# Fri3D_2020_Sweet4x4_01.net
KiCad netlist of a schematic drawn in Altium Designer
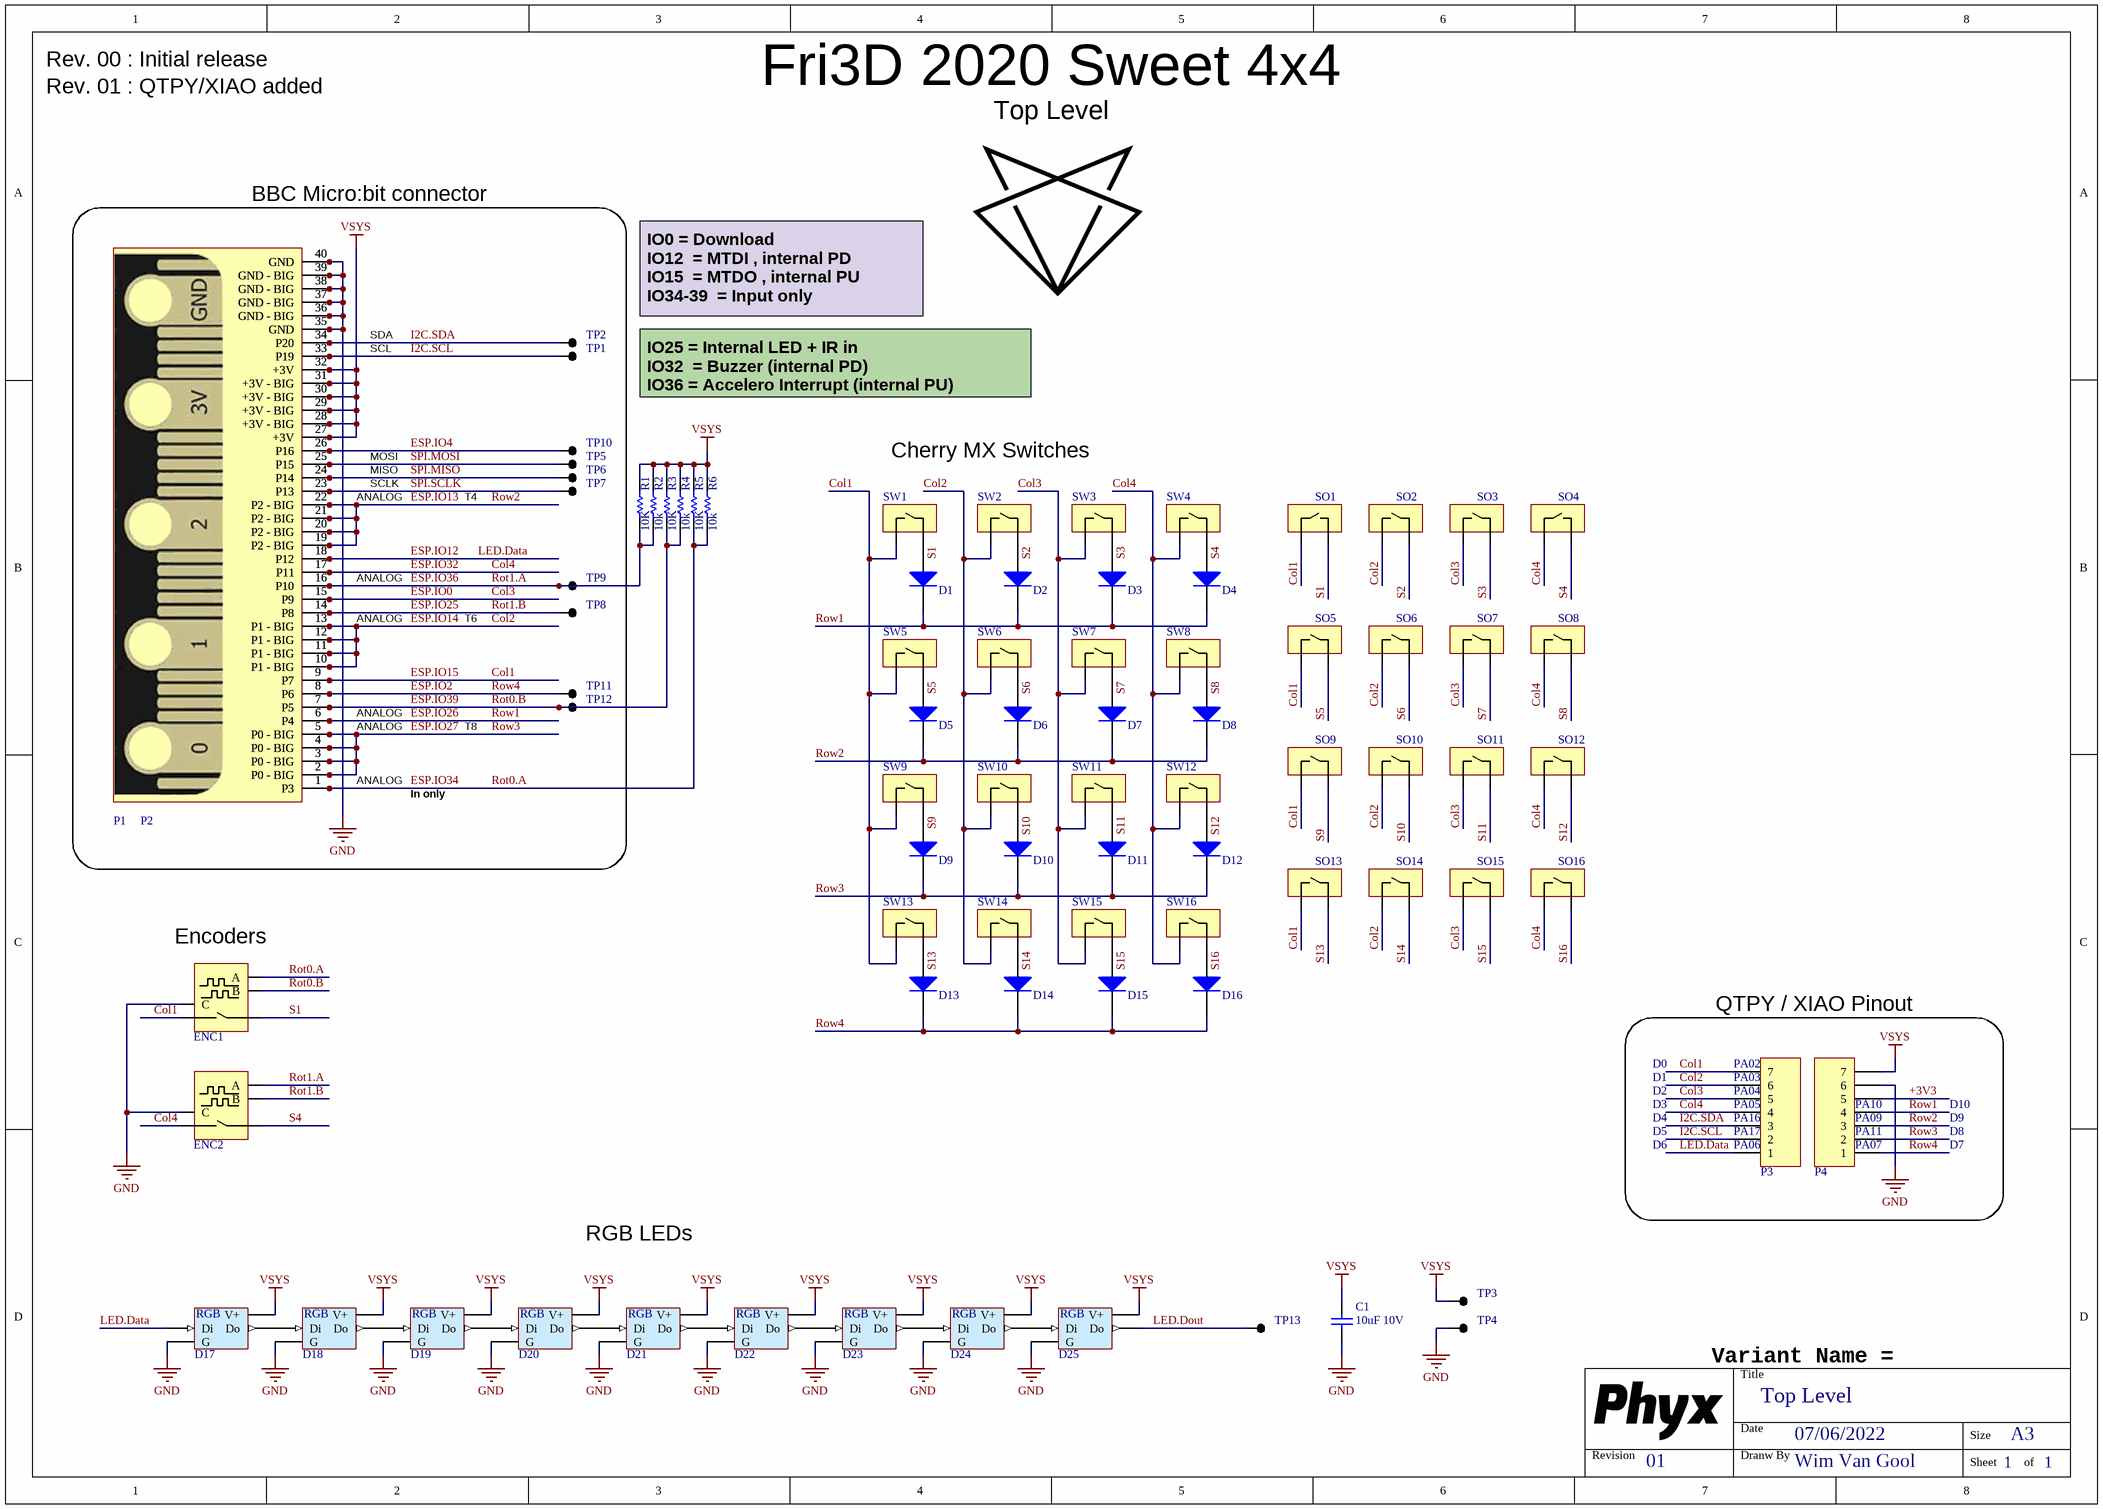
[diagram p0: Fri3D_2020_Sweet4x4_01.SchDoc]

(export (version "E")
  (design (tool "Eeschema 10.0.6"))
  (components
    (comp (ref "C1")
      (value "10uF 10V")
      (footprint "C0805_N")
      (description "Capacitor Ceramic")
      (fields (field (name "Comment") "CAP_CERAMIC"))
      (libsource (lib "Phyx_Components") (part "CAP_CERAMIC"))
    )
    (comp (ref "D1")
      (value "1N4148 100V 200mA 1Vf@10mA")
      (footprint "DO-35")
      (description "Default Diode")
      (libsource (lib "Phyx_Components") (part "DIODE_AC"))
    )
    (comp (ref "D2")
      (value "1N4148 100V 200mA 1Vf@10mA")
      (footprint "DO-35")
      (description "Default Diode")
      (libsource (lib "Phyx_Components") (part "DIODE_AC"))
    )
    (comp (ref "D3")
      (value "1N4148 100V 200mA 1Vf@10mA")
      (footprint "DO-35")
      (description "Default Diode")
      (libsource (lib "Phyx_Components") (part "DIODE_AC"))
    )
    (comp (ref "D4")
      (value "1N4148 100V 200mA 1Vf@10mA")
      (footprint "DO-35")
      (description "Default Diode")
      (libsource (lib "Phyx_Components") (part "DIODE_AC"))
    )
    (comp (ref "D5")
      (value "1N4148 100V 200mA 1Vf@10mA")
      (footprint "DO-35")
      (description "Default Diode")
      (libsource (lib "Phyx_Components") (part "DIODE_AC"))
    )
    (comp (ref "D6")
      (value "1N4148 100V 200mA 1Vf@10mA")
      (footprint "DO-35")
      (description "Default Diode")
      (libsource (lib "Phyx_Components") (part "DIODE_AC"))
    )
    (comp (ref "D7")
      (value "1N4148 100V 200mA 1Vf@10mA")
      (footprint "DO-35")
      (description "Default Diode")
      (libsource (lib "Phyx_Components") (part "DIODE_AC"))
    )
    (comp (ref "D8")
      (value "1N4148 100V 200mA 1Vf@10mA")
      (footprint "DO-35")
      (description "Default Diode")
      (libsource (lib "Phyx_Components") (part "DIODE_AC"))
    )
    (comp (ref "D9")
      (value "1N4148 100V 200mA 1Vf@10mA")
      (footprint "DO-35")
      (description "Default Diode")
      (libsource (lib "Phyx_Components") (part "DIODE_AC"))
    )
    (comp (ref "D10")
      (value "1N4148 100V 200mA 1Vf@10mA")
      (footprint "DO-35")
      (description "Default Diode")
      (libsource (lib "Phyx_Components") (part "DIODE_AC"))
    )
    (comp (ref "D11")
      (value "1N4148 100V 200mA 1Vf@10mA")
      (footprint "DO-35")
      (description "Default Diode")
      (libsource (lib "Phyx_Components") (part "DIODE_AC"))
    )
    (comp (ref "D12")
      (value "1N4148 100V 200mA 1Vf@10mA")
      (footprint "DO-35")
      (description "Default Diode")
      (libsource (lib "Phyx_Components") (part "DIODE_AC"))
    )
    (comp (ref "D13")
      (value "1N4148 100V 200mA 1Vf@10mA")
      (footprint "DO-35")
      (description "Default Diode")
      (libsource (lib "Phyx_Components") (part "DIODE_AC"))
    )
    (comp (ref "D14")
      (value "1N4148 100V 200mA 1Vf@10mA")
      (footprint "DO-35")
      (description "Default Diode")
      (libsource (lib "Phyx_Components") (part "DIODE_AC"))
    )
    (comp (ref "D15")
      (value "1N4148 100V 200mA 1Vf@10mA")
      (footprint "DO-35")
      (description "Default Diode")
      (libsource (lib "Phyx_Components") (part "DIODE_AC"))
    )
    (comp (ref "D16")
      (value "1N4148 100V 200mA 1Vf@10mA")
      (footprint "DO-35")
      (description "Default Diode")
      (libsource (lib "Phyx_Components") (part "DIODE_AC"))
    )
    (comp (ref "D17")
      (value "WS2812 based digital RGB LED 5050 Black package")
      (footprint "LED_5050_WS2812B_BLACK")
      (description "=Description")
      (libsource (lib "Phyx_Components") (part "LED_RGB_WS2812B_5050"))
    )
    (comp (ref "D18")
      (value "WS2812 based digital RGB LED 5050 Black package")
      (footprint "LED_5050_WS2812B_BLACK")
      (description "=Description")
      (libsource (lib "Phyx_Components") (part "LED_RGB_WS2812B_5050"))
    )
    (comp (ref "D19")
      (value "WS2812 based digital RGB LED 5050 Black package")
      (footprint "LED_5050_WS2812B_BLACK")
      (description "=Description")
      (libsource (lib "Phyx_Components") (part "LED_RGB_WS2812B_5050"))
    )
    (comp (ref "D20")
      (value "WS2812 based digital RGB LED 5050 Black package")
      (footprint "LED_5050_WS2812B_BLACK")
      (description "=Description")
      (libsource (lib "Phyx_Components") (part "LED_RGB_WS2812B_5050"))
    )
    (comp (ref "D21")
      (value "WS2812 based digital RGB LED 5050 Black package")
      (footprint "LED_5050_WS2812B_BLACK")
      (description "=Description")
      (libsource (lib "Phyx_Components") (part "LED_RGB_WS2812B_5050"))
    )
    (comp (ref "D22")
      (value "WS2812 based digital RGB LED 5050 Black package")
      (footprint "LED_5050_WS2812B_BLACK")
      (description "=Description")
      (libsource (lib "Phyx_Components") (part "LED_RGB_WS2812B_5050"))
    )
    (comp (ref "D23")
      (value "WS2812 based digital RGB LED 5050 Black package")
      (footprint "LED_5050_WS2812B_BLACK")
      (description "=Description")
      (libsource (lib "Phyx_Components") (part "LED_RGB_WS2812B_5050"))
    )
    (comp (ref "D24")
      (value "WS2812 based digital RGB LED 5050 Black package")
      (footprint "LED_5050_WS2812B_BLACK")
      (description "=Description")
      (libsource (lib "Phyx_Components") (part "LED_RGB_WS2812B_5050"))
    )
    (comp (ref "D25")
      (value "WS2812 based digital RGB LED 5050 Black package")
      (footprint "LED_5050_WS2812B_BLACK")
      (description "=Description")
      (libsource (lib "Phyx_Components") (part "LED_RGB_WS2812B_5050"))
    )
    (comp (ref "ENC1")
      (value "Rotary Encoder with Switch")
      (footprint "PEC11-4215F-S0024")
      (libsource (lib "Phyx_Components") (part "ROT_ENC_3P_SW"))
    )
    (comp (ref "ENC2")
      (value "Rotary Encoder with Switch")
      (footprint "PEC11-4215F-S0024")
      (libsource (lib "Phyx_Components") (part "ROT_ENC_3P_SW"))
    )
    (comp (ref "P1")
      (value "MicroBit 90deg connector Cylconn")
      (footprint "MicroBIT_CYLCONN_SMD_90")
      (libsource (lib "Phyx_Components") (part "Header 40_MicroBit"))
    )
    (comp (ref "P2")
      (value "MicroBit 180deg connector Cylconn")
      (footprint "MicroBIT_CYLCONN_SMD_180")
      (libsource (lib "Phyx_Components") (part "Header 40_MicroBit"))
    )
    (comp (ref "P3") (value "Header 7") (footprint "HDR1X7") (libsource (lib "") (part "Header 7_1")))
    (comp (ref "P4")
      (value "Header 7")
      (footprint "HDR1X7")
      (libsource (lib "Phyx_Components") (part "Header 7"))
    )
    (comp (ref "R1")
      (value "10K")
      (footprint "R0603_N")
      (fields (field (name "Comment") "RESISTOR"))
      (libsource (lib "Phyx_Components") (part "RESISTOR"))
    )
    (comp (ref "R2")
      (value "10k")
      (footprint "RES_10mm")
      (fields (field (name "Comment") "RESISTOR"))
      (libsource (lib "Phyx_Components") (part "RESISTOR"))
    )
    (comp (ref "R3")
      (value "10K")
      (footprint "R0603_N")
      (fields (field (name "Comment") "RESISTOR"))
      (libsource (lib "Phyx_Components") (part "RESISTOR"))
    )
    (comp (ref "R4")
      (value "10k")
      (footprint "RES_10mm")
      (fields (field (name "Comment") "RESISTOR"))
      (libsource (lib "Phyx_Components") (part "RESISTOR"))
    )
    (comp (ref "R5")
      (value "10K")
      (footprint "R0603_N")
      (fields (field (name "Comment") "RESISTOR"))
      (libsource (lib "Phyx_Components") (part "RESISTOR"))
    )
    (comp (ref "R6")
      (value "10k")
      (footprint "RES_10mm")
      (fields (field (name "Comment") "RESISTOR"))
      (libsource (lib "Phyx_Components") (part "RESISTOR"))
    )
    (comp (ref "SO1")
      (value "Kailh MX Socket")
      (footprint "Kailh_MX_Socket")
      (libsource (lib "") (part "SW_TACT_1"))
    )
    (comp (ref "SO2")
      (value "Kailh MX Socket")
      (footprint "Kailh_MX_Socket")
      (libsource (lib "Phyx_Components") (part "SW_TACT"))
    )
    (comp (ref "SO3")
      (value "Kailh MX Socket")
      (footprint "Kailh_MX_Socket")
      (libsource (lib "Phyx_Components") (part "SW_TACT"))
    )
    (comp (ref "SO4")
      (value "Kailh MX Socket")
      (footprint "Kailh_MX_Socket")
      (libsource (lib "") (part "SW_TACT_1"))
    )
    (comp (ref "SO5")
      (value "Kailh MX Socket")
      (footprint "Kailh_MX_Socket")
      (libsource (lib "Phyx_Components") (part "SW_TACT"))
    )
    (comp (ref "SO6")
      (value "Kailh MX Socket")
      (footprint "Kailh_MX_Socket")
      (libsource (lib "Phyx_Components") (part "SW_TACT"))
    )
    (comp (ref "SO7")
      (value "Kailh MX Socket")
      (footprint "Kailh_MX_Socket")
      (libsource (lib "Phyx_Components") (part "SW_TACT"))
    )
    (comp (ref "SO8")
      (value "Kailh MX Socket")
      (footprint "Kailh_MX_Socket")
      (libsource (lib "Phyx_Components") (part "SW_TACT"))
    )
    (comp (ref "SO9")
      (value "Kailh MX Socket")
      (footprint "Kailh_MX_Socket")
      (libsource (lib "Phyx_Components") (part "SW_TACT"))
    )
    (comp (ref "SO10")
      (value "Kailh MX Socket")
      (footprint "Kailh_MX_Socket")
      (libsource (lib "Phyx_Components") (part "SW_TACT"))
    )
    (comp (ref "SO11")
      (value "Kailh MX Socket")
      (footprint "Kailh_MX_Socket")
      (libsource (lib "Phyx_Components") (part "SW_TACT"))
    )
    (comp (ref "SO12")
      (value "Kailh MX Socket")
      (footprint "Kailh_MX_Socket")
      (libsource (lib "Phyx_Components") (part "SW_TACT"))
    )
    (comp (ref "SO13")
      (value "Kailh MX Socket")
      (footprint "Kailh_MX_Socket")
      (libsource (lib "Phyx_Components") (part "SW_TACT"))
    )
    (comp (ref "SO14")
      (value "Kailh MX Socket")
      (footprint "Kailh_MX_Socket")
      (libsource (lib "Phyx_Components") (part "SW_TACT"))
    )
    (comp (ref "SO15")
      (value "Kailh MX Socket")
      (footprint "Kailh_MX_Socket")
      (libsource (lib "Phyx_Components") (part "SW_TACT"))
    )
    (comp (ref "SO16")
      (value "Kailh MX Socket")
      (footprint "Kailh_MX_Socket")
      (libsource (lib "Phyx_Components") (part "SW_TACT"))
    )
    (comp (ref "SW1")
      (value "Cherry MX Blue")
      (footprint "Cherry_MX1A")
      (libsource (lib "Phyx_Components") (part "SW_TACT"))
    )
    (comp (ref "SW2")
      (value "Cherry MX Blue")
      (footprint "Cherry_MX1A")
      (libsource (lib "Phyx_Components") (part "SW_TACT"))
    )
    (comp (ref "SW3")
      (value "Cherry MX Blue")
      (footprint "Cherry_MX1A")
      (libsource (lib "Phyx_Components") (part "SW_TACT"))
    )
    (comp (ref "SW4")
      (value "Cherry MX Blue")
      (footprint "Cherry_MX1A")
      (libsource (lib "Phyx_Components") (part "SW_TACT"))
    )
    (comp (ref "SW5")
      (value "Cherry MX Blue")
      (footprint "Cherry_MX1A")
      (libsource (lib "Phyx_Components") (part "SW_TACT"))
    )
    (comp (ref "SW6")
      (value "Cherry MX Blue")
      (footprint "Cherry_MX1A")
      (libsource (lib "Phyx_Components") (part "SW_TACT"))
    )
    (comp (ref "SW7")
      (value "Cherry MX Blue")
      (footprint "Cherry_MX1A")
      (libsource (lib "Phyx_Components") (part "SW_TACT"))
    )
    (comp (ref "SW8")
      (value "Cherry MX Blue")
      (footprint "Cherry_MX1A")
      (libsource (lib "Phyx_Components") (part "SW_TACT"))
    )
    (comp (ref "SW9")
      (value "Cherry MX Blue")
      (footprint "Cherry_MX1A")
      (libsource (lib "Phyx_Components") (part "SW_TACT"))
    )
    (comp (ref "SW10")
      (value "Cherry MX Blue")
      (footprint "Cherry_MX1A")
      (libsource (lib "Phyx_Components") (part "SW_TACT"))
    )
    (comp (ref "SW11")
      (value "Cherry MX Blue")
      (footprint "Cherry_MX1A")
      (libsource (lib "Phyx_Components") (part "SW_TACT"))
    )
    (comp (ref "SW12")
      (value "Cherry MX Blue")
      (footprint "Cherry_MX1A")
      (libsource (lib "Phyx_Components") (part "SW_TACT"))
    )
    (comp (ref "SW13")
      (value "Cherry MX Blue")
      (footprint "Cherry_MX1A")
      (libsource (lib "Phyx_Components") (part "SW_TACT"))
    )
    (comp (ref "SW14")
      (value "Cherry MX Blue")
      (footprint "Cherry_MX1A")
      (libsource (lib "Phyx_Components") (part "SW_TACT"))
    )
    (comp (ref "SW15")
      (value "Cherry MX Blue")
      (footprint "Cherry_MX1A")
      (libsource (lib "Phyx_Components") (part "SW_TACT"))
    )
    (comp (ref "SW16")
      (value "Cherry MX Blue")
      (footprint "Cherry_MX1A")
      (libsource (lib "Phyx_Components") (part "SW_TACT"))
    )
    (comp (ref "TP1")
      (value "TEST_PAD")
      (footprint "TP_1.5mm_0.9mm")
      (libsource (lib "Phyx_Components") (part "TEST_PAD"))
    )
    (comp (ref "TP2")
      (value "TEST_PAD")
      (footprint "TP_1.5mm_0.9mm")
      (libsource (lib "Phyx_Components") (part "TEST_PAD"))
    )
    (comp (ref "TP3")
      (value "TEST_PAD")
      (footprint "TP_1.5mm_0.9mm")
      (libsource (lib "Phyx_Components") (part "TEST_PAD"))
    )
    (comp (ref "TP4")
      (value "TEST_PAD")
      (footprint "TP_1.5mm_0.9mm")
      (libsource (lib "Phyx_Components") (part "TEST_PAD"))
    )
    (comp (ref "TP5")
      (value "TEST_PAD")
      (footprint "TP_1.5mm_0.9mm")
      (libsource (lib "Phyx_Components") (part "TEST_PAD"))
    )
    (comp (ref "TP6")
      (value "TEST_PAD")
      (footprint "TP_1.5mm_0.9mm")
      (libsource (lib "Phyx_Components") (part "TEST_PAD"))
    )
    (comp (ref "TP7")
      (value "TEST_PAD")
      (footprint "TP_1.5mm_0.9mm")
      (libsource (lib "Phyx_Components") (part "TEST_PAD"))
    )
    (comp (ref "TP8")
      (value "TEST_PAD")
      (footprint "TP_1.5mm_0.9mm")
      (libsource (lib "Phyx_Components") (part "TEST_PAD"))
    )
    (comp (ref "TP9")
      (value "TEST_PAD")
      (footprint "TP_1.5mm_0.9mm")
      (libsource (lib "Phyx_Components") (part "TEST_PAD"))
    )
    (comp (ref "TP10")
      (value "TEST_PAD")
      (footprint "TP_1.5mm_0.9mm")
      (libsource (lib "Phyx_Components") (part "TEST_PAD"))
    )
    (comp (ref "TP11")
      (value "TEST_PAD")
      (footprint "TP_1.5mm_0.9mm")
      (libsource (lib "Phyx_Components") (part "TEST_PAD"))
    )
    (comp (ref "TP12")
      (value "TEST_PAD")
      (footprint "TP_1.5mm_0.9mm")
      (libsource (lib "Phyx_Components") (part "TEST_PAD"))
    )
    (comp (ref "TP13")
      (value "TEST_PAD")
      (footprint "TP_1.5mm_0.9mm")
      (libsource (lib "Phyx_Components") (part "TEST_PAD"))
    )
  )
  (nets
    (net (code "1") (name "/+3V3") (class "Default")
      (node (ref "P4") (pin "5") (pinfunction "5_5") (pintype "passive"))
    )
    (net (code "2") (name "/Col1") (class "Default")
      (node (ref "ENC1") (pin "1") (pinfunction "1_1") (pintype "passive"))
      (node (ref "P1") (pin "9") (pinfunction "P7_9") (pintype "passive"))
      (node (ref "P2") (pin "9") (pinfunction "P7_9") (pintype "passive"))
      (node (ref "P3") (pin "7") (pinfunction "7_7") (pintype "passive"))
      (node (ref "SO1") (pin "2") (pinfunction "2_2") (pintype "passive"))
      (node (ref "SO13") (pin "1") (pinfunction "1_1") (pintype "passive"))
      (node (ref "SO5") (pin "1") (pinfunction "1_1") (pintype "passive"))
      (node (ref "SO9") (pin "1") (pinfunction "1_1") (pintype "passive"))
      (node (ref "SW1") (pin "1") (pinfunction "1_1") (pintype "passive"))
      (node (ref "SW13") (pin "1") (pinfunction "1_1") (pintype "passive"))
      (node (ref "SW5") (pin "1") (pinfunction "1_1") (pintype "passive"))
      (node (ref "SW9") (pin "1") (pinfunction "1_1") (pintype "passive"))
    )
    (net (code "3") (name "/Col2") (class "Default")
      (node (ref "P1") (pin "10") (pinfunction "P1_-_BIG_10") (pintype "passive"))
      (node (ref "P1") (pin "11") (pinfunction "P1_-_BIG_11") (pintype "passive"))
      (node (ref "P1") (pin "12") (pinfunction "P1_-_BIG_12") (pintype "passive"))
      (node (ref "P1") (pin "13") (pinfunction "P1_-_BIG_13") (pintype "passive"))
      (node (ref "P2") (pin "10") (pinfunction "P1_-_BIG_10") (pintype "passive"))
      (node (ref "P2") (pin "11") (pinfunction "P1_-_BIG_11") (pintype "passive"))
      (node (ref "P2") (pin "12") (pinfunction "P1_-_BIG_12") (pintype "passive"))
      (node (ref "P2") (pin "13") (pinfunction "P1_-_BIG_13") (pintype "passive"))
      (node (ref "P3") (pin "6") (pinfunction "6_6") (pintype "passive"))
      (node (ref "SO10") (pin "1") (pinfunction "1_1") (pintype "passive"))
      (node (ref "SO14") (pin "1") (pinfunction "1_1") (pintype "passive"))
      (node (ref "SO2") (pin "1") (pinfunction "1_1") (pintype "passive"))
      (node (ref "SO6") (pin "1") (pinfunction "1_1") (pintype "passive"))
      (node (ref "SW10") (pin "1") (pinfunction "1_1") (pintype "passive"))
      (node (ref "SW14") (pin "1") (pinfunction "1_1") (pintype "passive"))
      (node (ref "SW2") (pin "1") (pinfunction "1_1") (pintype "passive"))
      (node (ref "SW6") (pin "1") (pinfunction "1_1") (pintype "passive"))
    )
    (net (code "4") (name "/Col3") (class "Default")
      (node (ref "P1") (pin "15") (pinfunction "P9_15") (pintype "passive"))
      (node (ref "P2") (pin "15") (pinfunction "P9_15") (pintype "passive"))
      (node (ref "P3") (pin "5") (pinfunction "5_5") (pintype "passive"))
      (node (ref "SO11") (pin "1") (pinfunction "1_1") (pintype "passive"))
      (node (ref "SO15") (pin "1") (pinfunction "1_1") (pintype "passive"))
      (node (ref "SO3") (pin "1") (pinfunction "1_1") (pintype "passive"))
      (node (ref "SO7") (pin "1") (pinfunction "1_1") (pintype "passive"))
      (node (ref "SW11") (pin "1") (pinfunction "1_1") (pintype "passive"))
      (node (ref "SW15") (pin "1") (pinfunction "1_1") (pintype "passive"))
      (node (ref "SW3") (pin "1") (pinfunction "1_1") (pintype "passive"))
      (node (ref "SW7") (pin "1") (pinfunction "1_1") (pintype "passive"))
    )
    (net (code "5") (name "/Col4") (class "Default")
      (node (ref "ENC2") (pin "1") (pinfunction "1_1") (pintype "passive"))
      (node (ref "P1") (pin "17") (pinfunction "P11_17") (pintype "passive"))
      (node (ref "P2") (pin "17") (pinfunction "P11_17") (pintype "passive"))
      (node (ref "P3") (pin "4") (pinfunction "4_4") (pintype "passive"))
      (node (ref "SO12") (pin "1") (pinfunction "1_1") (pintype "passive"))
      (node (ref "SO16") (pin "1") (pinfunction "1_1") (pintype "passive"))
      (node (ref "SO4") (pin "2") (pinfunction "2_2") (pintype "passive"))
      (node (ref "SO8") (pin "1") (pinfunction "1_1") (pintype "passive"))
      (node (ref "SW12") (pin "1") (pinfunction "1_1") (pintype "passive"))
      (node (ref "SW16") (pin "1") (pinfunction "1_1") (pintype "passive"))
      (node (ref "SW4") (pin "1") (pinfunction "1_1") (pintype "passive"))
      (node (ref "SW8") (pin "1") (pinfunction "1_1") (pintype "passive"))
    )
    (net (code "6") (name "/ESP.IO2") (class "Default")
      (node (ref "D13") (pin "C") (pinfunction "C_C") (pintype "passive"))
      (node (ref "D14") (pin "C") (pinfunction "C_C") (pintype "passive"))
      (node (ref "D15") (pin "C") (pinfunction "C_C") (pintype "passive"))
      (node (ref "D16") (pin "C") (pinfunction "C_C") (pintype "passive"))
      (node (ref "P1") (pin "8") (pinfunction "P6_8") (pintype "passive"))
      (node (ref "P2") (pin "8") (pinfunction "P6_8") (pintype "passive"))
      (node (ref "P4") (pin "1") (pinfunction "1_1") (pintype "passive"))
      (node (ref "TP11") (pin "1") (pinfunction "1_1") (pintype "passive"))
    )
    (net (code "7") (name "/ESP.IO4") (class "Default")
      (node (ref "P1") (pin "26") (pinfunction "P16_26") (pintype "passive"))
      (node (ref "P2") (pin "26") (pinfunction "P16_26") (pintype "passive"))
      (node (ref "TP10") (pin "1") (pinfunction "1_1") (pintype "passive"))
    )
    (net (code "8") (name "/ESP.IO12") (class "Default")
      (node (ref "D17") (pin "4") (pinfunction "Di_4") (pintype "input"))
      (node (ref "P1") (pin "18") (pinfunction "P12_18") (pintype "passive"))
      (node (ref "P2") (pin "18") (pinfunction "P12_18") (pintype "passive"))
      (node (ref "P3") (pin "1") (pinfunction "1_1") (pintype "passive"))
    )
    (net (code "9") (name "/ESP.IO13") (class "Default")
      (node (ref "D5") (pin "C") (pinfunction "C_C") (pintype "passive"))
      (node (ref "D6") (pin "C") (pinfunction "C_C") (pintype "passive"))
      (node (ref "D7") (pin "C") (pinfunction "C_C") (pintype "passive"))
      (node (ref "D8") (pin "C") (pinfunction "C_C") (pintype "passive"))
      (node (ref "P1") (pin "19") (pinfunction "P2_-_BIG_19") (pintype "passive"))
      (node (ref "P1") (pin "20") (pinfunction "P2_-_BIG_20") (pintype "passive"))
      (node (ref "P1") (pin "21") (pinfunction "P2_-_BIG_21") (pintype "passive"))
      (node (ref "P1") (pin "22") (pinfunction "P2_-_BIG_22") (pintype "passive"))
      (node (ref "P2") (pin "19") (pinfunction "P2_-_BIG_19") (pintype "passive"))
      (node (ref "P2") (pin "20") (pinfunction "P2_-_BIG_20") (pintype "passive"))
      (node (ref "P2") (pin "21") (pinfunction "P2_-_BIG_21") (pintype "passive"))
      (node (ref "P2") (pin "22") (pinfunction "P2_-_BIG_22") (pintype "passive"))
      (node (ref "P4") (pin "3") (pinfunction "3_3") (pintype "passive"))
    )
    (net (code "10") (name "/ESP.IO25") (class "Default")
      (node (ref "ENC2") (pin "B") (pinfunction "B_B") (pintype "passive"))
      (node (ref "P1") (pin "14") (pinfunction "P8_14") (pintype "passive"))
      (node (ref "P2") (pin "14") (pinfunction "P8_14") (pintype "passive"))
      (node (ref "TP8") (pin "1") (pinfunction "1_1") (pintype "passive"))
    )
    (net (code "11") (name "/ESP.IO26") (class "Default")
      (node (ref "D1") (pin "C") (pinfunction "C_C") (pintype "passive"))
      (node (ref "D2") (pin "C") (pinfunction "C_C") (pintype "passive"))
      (node (ref "D3") (pin "C") (pinfunction "C_C") (pintype "passive"))
      (node (ref "D4") (pin "C") (pinfunction "C_C") (pintype "passive"))
      (node (ref "P1") (pin "6") (pinfunction "P4_6") (pintype "passive"))
      (node (ref "P2") (pin "6") (pinfunction "P4_6") (pintype "passive"))
      (node (ref "P4") (pin "4") (pinfunction "4_4") (pintype "passive"))
    )
    (net (code "12") (name "/ESP.IO27") (class "Default")
      (node (ref "D10") (pin "C") (pinfunction "C_C") (pintype "passive"))
      (node (ref "D11") (pin "C") (pinfunction "C_C") (pintype "passive"))
      (node (ref "D12") (pin "C") (pinfunction "C_C") (pintype "passive"))
      (node (ref "D9") (pin "C") (pinfunction "C_C") (pintype "passive"))
      (node (ref "P1") (pin "2") (pinfunction "P0_-_BIG_2") (pintype "passive"))
      (node (ref "P1") (pin "3") (pinfunction "P0_-_BIG_3") (pintype "passive"))
      (node (ref "P1") (pin "4") (pinfunction "P0_-_BIG_4") (pintype "passive"))
      (node (ref "P1") (pin "5") (pinfunction "P0_-_BIG_5") (pintype "passive"))
      (node (ref "P2") (pin "2") (pinfunction "P0_-_BIG_2") (pintype "passive"))
      (node (ref "P2") (pin "3") (pinfunction "P0_-_BIG_3") (pintype "passive"))
      (node (ref "P2") (pin "4") (pinfunction "P0_-_BIG_4") (pintype "passive"))
      (node (ref "P2") (pin "5") (pinfunction "P0_-_BIG_5") (pintype "passive"))
      (node (ref "P4") (pin "2") (pinfunction "2_2") (pintype "passive"))
    )
    (net (code "13") (name "/ESP.IO34") (class "Default")
      (node (ref "ENC1") (pin "A") (pinfunction "A_A") (pintype "passive"))
      (node (ref "P1") (pin "1") (pinfunction "P3_1") (pintype "passive"))
      (node (ref "P2") (pin "1") (pinfunction "P3_1") (pintype "passive"))
      (node (ref "R5") (pin "2") (pinfunction "2_2") (pintype "passive"))
      (node (ref "R6") (pin "2") (pinfunction "2_2") (pintype "passive"))
    )
    (net (code "14") (name "/ESP.IO36") (class "Default")
      (node (ref "ENC2") (pin "A") (pinfunction "A_A") (pintype "passive"))
      (node (ref "P1") (pin "16") (pinfunction "P10_16") (pintype "passive"))
      (node (ref "P2") (pin "16") (pinfunction "P10_16") (pintype "passive"))
      (node (ref "R1") (pin "2") (pinfunction "2_2") (pintype "passive"))
      (node (ref "R2") (pin "2") (pinfunction "2_2") (pintype "passive"))
      (node (ref "TP9") (pin "1") (pinfunction "1_1") (pintype "passive"))
    )
    (net (code "15") (name "/ESP.IO39") (class "Default")
      (node (ref "ENC1") (pin "B") (pinfunction "B_B") (pintype "passive"))
      (node (ref "P1") (pin "7") (pinfunction "P5_7") (pintype "passive"))
      (node (ref "P2") (pin "7") (pinfunction "P5_7") (pintype "passive"))
      (node (ref "R3") (pin "2") (pinfunction "2_2") (pintype "passive"))
      (node (ref "R4") (pin "2") (pinfunction "2_2") (pintype "passive"))
      (node (ref "TP12") (pin "1") (pinfunction "1_1") (pintype "passive"))
    )
    (net (code "16") (name "/I2C.SCL") (class "Default")
      (node (ref "P1") (pin "33") (pinfunction "P19_33") (pintype "passive"))
      (node (ref "P2") (pin "33") (pinfunction "P19_33") (pintype "passive"))
      (node (ref "P3") (pin "2") (pinfunction "2_2") (pintype "passive"))
      (node (ref "TP1") (pin "1") (pinfunction "1_1") (pintype "passive"))
    )
    (net (code "17") (name "/I2C.SDA") (class "Default")
      (node (ref "P1") (pin "34") (pinfunction "P20_34") (pintype "passive"))
      (node (ref "P2") (pin "34") (pinfunction "P20_34") (pintype "passive"))
      (node (ref "P3") (pin "3") (pinfunction "3_3") (pintype "passive"))
      (node (ref "TP2") (pin "1") (pinfunction "1_1") (pintype "passive"))
    )
    (net (code "18") (name "/LED.Dout") (class "Default")
      (node (ref "D25") (pin "2") (pinfunction "Do_2") (pintype "output"))
      (node (ref "TP13") (pin "1") (pinfunction "1_1") (pintype "passive"))
    )
    (net (code "19") (name "/S1") (class "Default")
      (node (ref "D1") (pin "A") (pinfunction "A_A") (pintype "passive"))
      (node (ref "ENC1") (pin "2") (pinfunction "2_2") (pintype "passive"))
      (node (ref "SO1") (pin "1") (pinfunction "1_1") (pintype "passive"))
      (node (ref "SW1") (pin "2") (pinfunction "2_2") (pintype "passive"))
    )
    (net (code "20") (name "/S2") (class "Default")
      (node (ref "D2") (pin "A") (pinfunction "A_A") (pintype "passive"))
      (node (ref "SO2") (pin "2") (pinfunction "2_2") (pintype "passive"))
      (node (ref "SW2") (pin "2") (pinfunction "2_2") (pintype "passive"))
    )
    (net (code "21") (name "/S3") (class "Default")
      (node (ref "D3") (pin "A") (pinfunction "A_A") (pintype "passive"))
      (node (ref "SO3") (pin "2") (pinfunction "2_2") (pintype "passive"))
      (node (ref "SW3") (pin "2") (pinfunction "2_2") (pintype "passive"))
    )
    (net (code "22") (name "/S4") (class "Default")
      (node (ref "D4") (pin "A") (pinfunction "A_A") (pintype "passive"))
      (node (ref "ENC2") (pin "2") (pinfunction "2_2") (pintype "passive"))
      (node (ref "SO4") (pin "1") (pinfunction "1_1") (pintype "passive"))
      (node (ref "SW4") (pin "2") (pinfunction "2_2") (pintype "passive"))
    )
    (net (code "23") (name "/S5") (class "Default")
      (node (ref "D5") (pin "A") (pinfunction "A_A") (pintype "passive"))
      (node (ref "SO5") (pin "2") (pinfunction "2_2") (pintype "passive"))
      (node (ref "SW5") (pin "2") (pinfunction "2_2") (pintype "passive"))
    )
    (net (code "24") (name "/S6") (class "Default")
      (node (ref "D6") (pin "A") (pinfunction "A_A") (pintype "passive"))
      (node (ref "SO6") (pin "2") (pinfunction "2_2") (pintype "passive"))
      (node (ref "SW6") (pin "2") (pinfunction "2_2") (pintype "passive"))
    )
    (net (code "25") (name "/S7") (class "Default")
      (node (ref "D7") (pin "A") (pinfunction "A_A") (pintype "passive"))
      (node (ref "SO7") (pin "2") (pinfunction "2_2") (pintype "passive"))
      (node (ref "SW7") (pin "2") (pinfunction "2_2") (pintype "passive"))
    )
    (net (code "26") (name "/S8") (class "Default")
      (node (ref "D8") (pin "A") (pinfunction "A_A") (pintype "passive"))
      (node (ref "SO8") (pin "2") (pinfunction "2_2") (pintype "passive"))
      (node (ref "SW8") (pin "2") (pinfunction "2_2") (pintype "passive"))
    )
    (net (code "27") (name "/S9") (class "Default")
      (node (ref "D9") (pin "A") (pinfunction "A_A") (pintype "passive"))
      (node (ref "SO9") (pin "2") (pinfunction "2_2") (pintype "passive"))
      (node (ref "SW9") (pin "2") (pinfunction "2_2") (pintype "passive"))
    )
    (net (code "28") (name "/S10") (class "Default")
      (node (ref "D10") (pin "A") (pinfunction "A_A") (pintype "passive"))
      (node (ref "SO10") (pin "2") (pinfunction "2_2") (pintype "passive"))
      (node (ref "SW10") (pin "2") (pinfunction "2_2") (pintype "passive"))
    )
    (net (code "29") (name "/S11") (class "Default")
      (node (ref "D11") (pin "A") (pinfunction "A_A") (pintype "passive"))
      (node (ref "SO11") (pin "2") (pinfunction "2_2") (pintype "passive"))
      (node (ref "SW11") (pin "2") (pinfunction "2_2") (pintype "passive"))
    )
    (net (code "30") (name "/S12") (class "Default")
      (node (ref "D12") (pin "A") (pinfunction "A_A") (pintype "passive"))
      (node (ref "SO12") (pin "2") (pinfunction "2_2") (pintype "passive"))
      (node (ref "SW12") (pin "2") (pinfunction "2_2") (pintype "passive"))
    )
    (net (code "31") (name "/S13") (class "Default")
      (node (ref "D13") (pin "A") (pinfunction "A_A") (pintype "passive"))
      (node (ref "SO13") (pin "2") (pinfunction "2_2") (pintype "passive"))
      (node (ref "SW13") (pin "2") (pinfunction "2_2") (pintype "passive"))
    )
    (net (code "32") (name "/S14") (class "Default")
      (node (ref "D14") (pin "A") (pinfunction "A_A") (pintype "passive"))
      (node (ref "SO14") (pin "2") (pinfunction "2_2") (pintype "passive"))
      (node (ref "SW14") (pin "2") (pinfunction "2_2") (pintype "passive"))
    )
    (net (code "33") (name "/S15") (class "Default")
      (node (ref "D15") (pin "A") (pinfunction "A_A") (pintype "passive"))
      (node (ref "SO15") (pin "2") (pinfunction "2_2") (pintype "passive"))
      (node (ref "SW15") (pin "2") (pinfunction "2_2") (pintype "passive"))
    )
    (net (code "34") (name "/S16") (class "Default")
      (node (ref "D16") (pin "A") (pinfunction "A_A") (pintype "passive"))
      (node (ref "SO16") (pin "2") (pinfunction "2_2") (pintype "passive"))
      (node (ref "SW16") (pin "2") (pinfunction "2_2") (pintype "passive"))
    )
    (net (code "35") (name "/SPI.MISO") (class "Default")
      (node (ref "P1") (pin "24") (pinfunction "P14_24") (pintype "passive"))
      (node (ref "P2") (pin "24") (pinfunction "P14_24") (pintype "passive"))
      (node (ref "TP6") (pin "1") (pinfunction "1_1") (pintype "passive"))
    )
    (net (code "36") (name "/SPI.MOSI") (class "Default")
      (node (ref "P1") (pin "25") (pinfunction "P15_25") (pintype "passive"))
      (node (ref "P2") (pin "25") (pinfunction "P15_25") (pintype "passive"))
      (node (ref "TP5") (pin "1") (pinfunction "1_1") (pintype "passive"))
    )
    (net (code "37") (name "/SPI.SCLK") (class "Default")
      (node (ref "P1") (pin "23") (pinfunction "P13_23") (pintype "passive"))
      (node (ref "P2") (pin "23") (pinfunction "P13_23") (pintype "passive"))
      (node (ref "TP7") (pin "1") (pinfunction "1_1") (pintype "passive"))
    )
    (net (code "38") (name "GND") (class "Default")
      (node (ref "C1") (pin "2") (pinfunction "2_2") (pintype "passive"))
      (node (ref "D17") (pin "3") (pinfunction "G_3") (pintype "power_in"))
      (node (ref "D18") (pin "3") (pinfunction "G_3") (pintype "power_in"))
      (node (ref "D19") (pin "3") (pinfunction "G_3") (pintype "power_in"))
      (node (ref "D20") (pin "3") (pinfunction "G_3") (pintype "power_in"))
      (node (ref "D21") (pin "3") (pinfunction "G_3") (pintype "power_in"))
      (node (ref "D22") (pin "3") (pinfunction "G_3") (pintype "power_in"))
      (node (ref "D23") (pin "3") (pinfunction "G_3") (pintype "power_in"))
      (node (ref "D24") (pin "3") (pinfunction "G_3") (pintype "power_in"))
      (node (ref "D25") (pin "3") (pinfunction "G_3") (pintype "power_in"))
      (node (ref "ENC1") (pin "C") (pinfunction "C_C") (pintype "passive"))
      (node (ref "ENC2") (pin "C") (pinfunction "C_C") (pintype "passive"))
      (node (ref "P1") (pin "35") (pinfunction "GND_35") (pintype "passive"))
      (node (ref "P1") (pin "36") (pinfunction "GND_-_BIG_36") (pintype "passive"))
      (node (ref "P1") (pin "37") (pinfunction "GND_-_BIG_37") (pintype "passive"))
      (node (ref "P1") (pin "38") (pinfunction "GND_-_BIG_38") (pintype "passive"))
      (node (ref "P1") (pin "39") (pinfunction "GND_-_BIG_39") (pintype "passive"))
      (node (ref "P1") (pin "40") (pinfunction "GND_40") (pintype "passive"))
      (node (ref "P2") (pin "35") (pinfunction "GND_35") (pintype "passive"))
      (node (ref "P2") (pin "36") (pinfunction "GND_-_BIG_36") (pintype "passive"))
      (node (ref "P2") (pin "37") (pinfunction "GND_-_BIG_37") (pintype "passive"))
      (node (ref "P2") (pin "38") (pinfunction "GND_-_BIG_38") (pintype "passive"))
      (node (ref "P2") (pin "39") (pinfunction "GND_-_BIG_39") (pintype "passive"))
      (node (ref "P2") (pin "40") (pinfunction "GND_40") (pintype "passive"))
      (node (ref "P4") (pin "6") (pinfunction "6_6") (pintype "passive"))
      (node (ref "TP4") (pin "1") (pinfunction "1_1") (pintype "passive"))
    )
    (net (code "39") (name "Net-(D17-Do)") (class "Default")
      (node (ref "D17") (pin "2") (pinfunction "Do_2") (pintype "output"))
      (node (ref "D18") (pin "4") (pinfunction "Di_4") (pintype "input"))
    )
    (net (code "40") (name "Net-(D18-Do)") (class "Default")
      (node (ref "D18") (pin "2") (pinfunction "Do_2") (pintype "output"))
      (node (ref "D19") (pin "4") (pinfunction "Di_4") (pintype "input"))
    )
    (net (code "41") (name "Net-(D19-Do)") (class "Default")
      (node (ref "D19") (pin "2") (pinfunction "Do_2") (pintype "output"))
      (node (ref "D20") (pin "4") (pinfunction "Di_4") (pintype "input"))
    )
    (net (code "42") (name "Net-(D20-Do)") (class "Default")
      (node (ref "D20") (pin "2") (pinfunction "Do_2") (pintype "output"))
      (node (ref "D21") (pin "4") (pinfunction "Di_4") (pintype "input"))
    )
    (net (code "43") (name "Net-(D21-Do)") (class "Default")
      (node (ref "D21") (pin "2") (pinfunction "Do_2") (pintype "output"))
      (node (ref "D22") (pin "4") (pinfunction "Di_4") (pintype "input"))
    )
    (net (code "44") (name "Net-(D22-Do)") (class "Default")
      (node (ref "D22") (pin "2") (pinfunction "Do_2") (pintype "output"))
      (node (ref "D23") (pin "4") (pinfunction "Di_4") (pintype "input"))
    )
    (net (code "45") (name "Net-(D23-Do)") (class "Default")
      (node (ref "D23") (pin "2") (pinfunction "Do_2") (pintype "output"))
      (node (ref "D24") (pin "4") (pinfunction "Di_4") (pintype "input"))
    )
    (net (code "46") (name "Net-(D24-Do)") (class "Default")
      (node (ref "D24") (pin "2") (pinfunction "Do_2") (pintype "output"))
      (node (ref "D25") (pin "4") (pinfunction "Di_4") (pintype "input"))
    )
    (net (code "47") (name "VSYS") (class "Default")
      (node (ref "C1") (pin "1") (pinfunction "1_1") (pintype "passive"))
      (node (ref "D17") (pin "1") (pinfunction "V+_1") (pintype "power_in"))
      (node (ref "D18") (pin "1") (pinfunction "V+_1") (pintype "power_in"))
      (node (ref "D19") (pin "1") (pinfunction "V+_1") (pintype "power_in"))
      (node (ref "D20") (pin "1") (pinfunction "V+_1") (pintype "power_in"))
      (node (ref "D21") (pin "1") (pinfunction "V+_1") (pintype "power_in"))
      (node (ref "D22") (pin "1") (pinfunction "V+_1") (pintype "power_in"))
      (node (ref "D23") (pin "1") (pinfunction "V+_1") (pintype "power_in"))
      (node (ref "D24") (pin "1") (pinfunction "V+_1") (pintype "power_in"))
      (node (ref "D25") (pin "1") (pinfunction "V+_1") (pintype "power_in"))
      (node (ref "P1") (pin "27") (pinfunction "+3V_27") (pintype "passive"))
      (node (ref "P1") (pin "28") (pinfunction "+3V_-_BIG_28") (pintype "passive"))
      (node (ref "P1") (pin "29") (pinfunction "+3V_-_BIG_29") (pintype "passive"))
      (node (ref "P1") (pin "30") (pinfunction "+3V_-_BIG_30") (pintype "passive"))
      (node (ref "P1") (pin "31") (pinfunction "+3V_-_BIG_31") (pintype "passive"))
      (node (ref "P1") (pin "32") (pinfunction "+3V_32") (pintype "passive"))
      (node (ref "P2") (pin "27") (pinfunction "+3V_27") (pintype "passive"))
      (node (ref "P2") (pin "28") (pinfunction "+3V_-_BIG_28") (pintype "passive"))
      (node (ref "P2") (pin "29") (pinfunction "+3V_-_BIG_29") (pintype "passive"))
      (node (ref "P2") (pin "30") (pinfunction "+3V_-_BIG_30") (pintype "passive"))
      (node (ref "P2") (pin "31") (pinfunction "+3V_-_BIG_31") (pintype "passive"))
      (node (ref "P2") (pin "32") (pinfunction "+3V_32") (pintype "passive"))
      (node (ref "P4") (pin "7") (pinfunction "7_7") (pintype "passive"))
      (node (ref "R1") (pin "1") (pinfunction "1_1") (pintype "passive"))
      (node (ref "R2") (pin "1") (pinfunction "1_1") (pintype "passive"))
      (node (ref "R3") (pin "1") (pinfunction "1_1") (pintype "passive"))
      (node (ref "R4") (pin "1") (pinfunction "1_1") (pintype "passive"))
      (node (ref "R5") (pin "1") (pinfunction "1_1") (pintype "passive"))
      (node (ref "R6") (pin "1") (pinfunction "1_1") (pintype "passive"))
      (node (ref "TP3") (pin "1") (pinfunction "1_1") (pintype "passive"))
    )
  )
)
